# Sens_BH1750.net
KiCad netlist of a schematic drawn in EAGLE
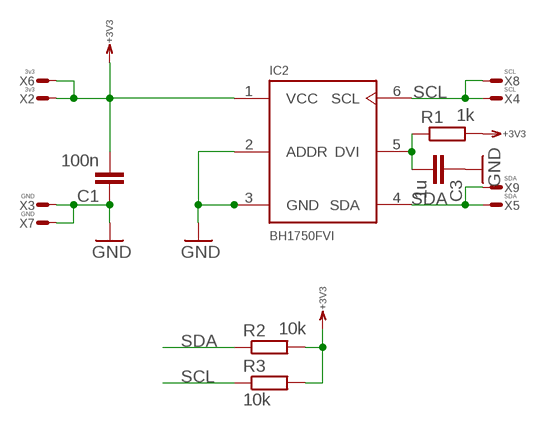
[diagram p0: schematic, sheet 1]

(export (version "E")
  (design (tool "Eeschema 10.0.6"))
  (components
    (comp (ref "C1")
      (value "100n")
      (footprint "eagle-import:0603")
      (libsource (lib "eagle-import") (part "C0603"))
    )
    (comp (ref "C3")
      (value "1u")
      (footprint "eagle-import:0603")
      (libsource (lib "eagle-import") (part "C0603"))
    )
    (comp (ref "IC2")
      (value "BH1750FVI")
      (footprint "eagle-import:WSOF6I")
      (libsource (lib "eagle-import") (part "BH1750FVI"))
    )
    (comp (ref "R1")
      (value "1k")
      (footprint "eagle-import:0603")
      (libsource (lib "eagle-import") (part "R0603"))
    )
    (comp (ref "R2")
      (value "10k")
      (footprint "eagle-import:0603")
      (libsource (lib "eagle-import") (part "R0603"))
    )
    (comp (ref "R3")
      (value "10k")
      (footprint "eagle-import:0603")
      (libsource (lib "eagle-import") (part "R0603"))
    )
    (comp (ref "X2")
      (value "3v3")
      (footprint "eagle-import:T1.6_0.9")
      (libsource (lib "eagle-import") (part "WIREPADT1.6/0.9"))
    )
    (comp (ref "X3")
      (value "GND")
      (footprint "eagle-import:T1.6_0.9")
      (libsource (lib "eagle-import") (part "WIREPADT1.6/0.9"))
    )
    (comp (ref "X4")
      (value "SCL")
      (footprint "eagle-import:T1.6_0.9")
      (libsource (lib "eagle-import") (part "WIREPADT1.6/0.9"))
    )
    (comp (ref "X5")
      (value "SDA")
      (footprint "eagle-import:T1.6_0.9")
      (libsource (lib "eagle-import") (part "WIREPADT1.6/0.9"))
    )
    (comp (ref "X6")
      (value "3v3")
      (footprint "eagle-import:T1.6_0.9")
      (libsource (lib "eagle-import") (part "WIREPADT1.6/0.9"))
    )
    (comp (ref "X7")
      (value "GND")
      (footprint "eagle-import:T1.6_0.9")
      (libsource (lib "eagle-import") (part "WIREPADT1.6/0.9"))
    )
    (comp (ref "X8")
      (value "SCL")
      (footprint "eagle-import:T1.6_0.9")
      (libsource (lib "eagle-import") (part "WIREPADT1.6/0.9"))
    )
    (comp (ref "X9")
      (value "SDA")
      (footprint "eagle-import:T1.6_0.9")
      (libsource (lib "eagle-import") (part "WIREPADT1.6/0.9"))
    )
  )
  (nets
    (net (code "1") (name "+3V3") (class "Default")
      (node (ref "C1") (pin "2") (pinfunction "2_2") (pintype "passive"))
      (node (ref "IC2") (pin "1") (pinfunction "VCC_1") (pintype "input"))
      (node (ref "R1") (pin "2") (pinfunction "2_2") (pintype "passive"))
      (node (ref "R2") (pin "2") (pinfunction "2_2") (pintype "passive"))
      (node (ref "R3") (pin "2") (pinfunction "2_2") (pintype "passive"))
      (node (ref "X2") (pin "1") (pinfunction "S_1") (pintype "passive"))
      (node (ref "X6") (pin "1") (pinfunction "S_1") (pintype "passive"))
    )
    (net (code "2") (name "/SCL") (class "Default")
      (node (ref "IC2") (pin "6") (pinfunction "SCL_6") (pintype "bidirectional"))
      (node (ref "R3") (pin "1") (pinfunction "1_1") (pintype "passive"))
      (node (ref "X4") (pin "1") (pinfunction "S_1") (pintype "passive"))
      (node (ref "X8") (pin "1") (pinfunction "S_1") (pintype "passive"))
    )
    (net (code "3") (name "/SDA") (class "Default")
      (node (ref "IC2") (pin "4") (pinfunction "SDA_4") (pintype "bidirectional"))
      (node (ref "R2") (pin "1") (pinfunction "1_1") (pintype "passive"))
      (node (ref "X5") (pin "1") (pinfunction "S_1") (pintype "passive"))
      (node (ref "X9") (pin "1") (pinfunction "S_1") (pintype "passive"))
    )
    (net (code "4") (name "GND") (class "Default")
      (node (ref "C1") (pin "1") (pinfunction "1_1") (pintype "passive"))
      (node (ref "C3") (pin "1") (pinfunction "1_1") (pintype "passive"))
      (node (ref "IC2") (pin "2") (pinfunction "ADDR_2") (pintype "input"))
      (node (ref "IC2") (pin "3") (pinfunction "GND_3") (pintype "input"))
      (node (ref "X3") (pin "1") (pinfunction "S_1") (pintype "passive"))
      (node (ref "X7") (pin "1") (pinfunction "S_1") (pintype "passive"))
    )
    (net (code "5") (name "Net-(IC2-DVI)") (class "Default")
      (node (ref "C3") (pin "2") (pinfunction "2_2") (pintype "passive"))
      (node (ref "IC2") (pin "5") (pinfunction "DVI_5") (pintype "input"))
      (node (ref "R1") (pin "1") (pinfunction "1_1") (pintype "passive"))
    )
  )
)
